# TM1637_Display-Board_simple.net
KiCad netlist of a schematic drawn in EAGLE
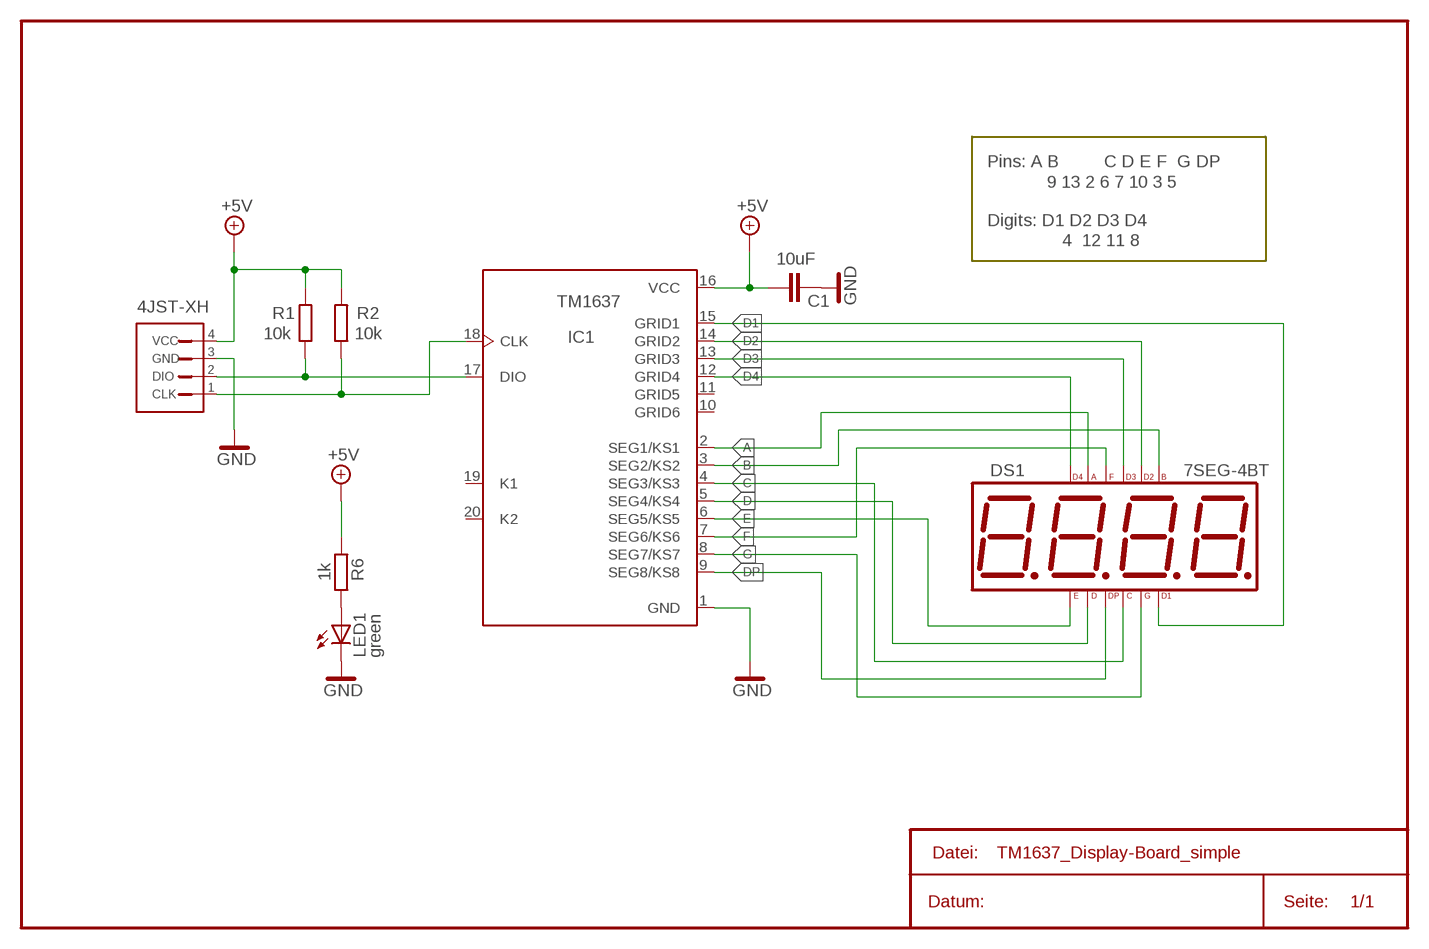
[diagram p0: schematic, sheet 1]

(export (version "E")
  (design (tool "Eeschema 10.0.6"))
  (components
    (comp (ref "1")
      (value "4JST-XH")
      (footprint "eagle-import:4JST-XH")
      (libsource (lib "eagle-import") (part "4JST-XH"))
    )
    (comp (ref "C1")
      (value "10uF")
      (footprint "eagle-import:C0805")
      (libsource (lib "eagle-import") (part "C-EUC0805"))
    )
    (comp (ref "DS1")
      (value "7SEG-4BT")
      (footprint "eagle-import:7SEG-14-4BIT")
      (libsource (lib "eagle-import") (part "7SEG-4BT"))
    )
    (comp (ref "IC1")
      (value "TM1637")
      (footprint "eagle-import:SOP-20")
      (libsource (lib "eagle-import") (part "TM1637"))
    )
    (comp (ref "LED1")
      (value "green")
      (footprint "eagle-import:CHIPLED_0603")
      (libsource (lib "eagle-import") (part "LEDCHIPLED_0603"))
    )
    (comp (ref "R1")
      (value "10k")
      (footprint "eagle-import:R0603")
      (libsource (lib "eagle-import") (part "R-EU_R0603"))
    )
    (comp (ref "R2")
      (value "10k")
      (footprint "eagle-import:R0603")
      (libsource (lib "eagle-import") (part "R-EU_R0603"))
    )
    (comp (ref "R6")
      (value "1k")
      (footprint "eagle-import:R0603")
      (libsource (lib "eagle-import") (part "R-EU_R0603"))
    )
  )
  (nets
    (net (code "1") (name "+5V") (class "Default")
      (node (ref "1") (pin "1") (pinfunction "1_1") (pintype "passive"))
      (node (ref "C1") (pin "1") (pinfunction "1_1") (pintype "passive"))
      (node (ref "IC1") (pin "16") (pinfunction "VCC_16") (pintype "bidirectional"))
      (node (ref "R1") (pin "2") (pinfunction "2_2") (pintype "passive"))
      (node (ref "R2") (pin "2") (pinfunction "2_2") (pintype "passive"))
      (node (ref "R6") (pin "1") (pinfunction "1_1") (pintype "passive"))
    )
    (net (code "2") (name "A") (class "Default")
      (node (ref "DS1") (pin "A") (pinfunction "A_A") (pintype "bidirectional"))
      (node (ref "IC1") (pin "2") (pinfunction "SEG1/KS1_2") (pintype "bidirectional"))
    )
    (net (code "3") (name "B") (class "Default")
      (node (ref "DS1") (pin "B") (pinfunction "B_B") (pintype "bidirectional"))
      (node (ref "IC1") (pin "3") (pinfunction "SEG2/KS2_3") (pintype "bidirectional"))
    )
    (net (code "4") (name "C") (class "Default")
      (node (ref "DS1") (pin "C") (pinfunction "C_C") (pintype "bidirectional"))
      (node (ref "IC1") (pin "4") (pinfunction "SEG3/KS3_4") (pintype "bidirectional"))
    )
    (net (code "5") (name "D") (class "Default")
      (node (ref "DS1") (pin "D") (pinfunction "D_D") (pintype "bidirectional"))
      (node (ref "IC1") (pin "5") (pinfunction "SEG4/KS4_5") (pintype "bidirectional"))
    )
    (net (code "6") (name "D1") (class "Default")
      (node (ref "DS1") (pin "D1") (pinfunction "D1_D1") (pintype "bidirectional"))
      (node (ref "IC1") (pin "15") (pinfunction "GRID1_15") (pintype "bidirectional"))
    )
    (net (code "7") (name "D2") (class "Default")
      (node (ref "DS1") (pin "D2") (pinfunction "D2_D2") (pintype "bidirectional"))
      (node (ref "IC1") (pin "14") (pinfunction "GRID2_14") (pintype "bidirectional"))
    )
    (net (code "8") (name "D3") (class "Default")
      (node (ref "DS1") (pin "D3") (pinfunction "D3_D3") (pintype "bidirectional"))
      (node (ref "IC1") (pin "13") (pinfunction "GRID3_13") (pintype "bidirectional"))
    )
    (net (code "9") (name "D4") (class "Default")
      (node (ref "DS1") (pin "D4") (pinfunction "D4_D4") (pintype "bidirectional"))
      (node (ref "IC1") (pin "12") (pinfunction "GRID4_12") (pintype "bidirectional"))
    )
    (net (code "10") (name "DP") (class "Default")
      (node (ref "DS1") (pin "DP") (pinfunction "DP_DP") (pintype "bidirectional"))
      (node (ref "IC1") (pin "9") (pinfunction "SEG8/KS8_9") (pintype "bidirectional"))
    )
    (net (code "11") (name "E") (class "Default")
      (node (ref "DS1") (pin "E") (pinfunction "E_E") (pintype "bidirectional"))
      (node (ref "IC1") (pin "6") (pinfunction "SEG5/KS5_6") (pintype "bidirectional"))
    )
    (net (code "12") (name "F") (class "Default")
      (node (ref "DS1") (pin "F") (pinfunction "F_F") (pintype "bidirectional"))
      (node (ref "IC1") (pin "7") (pinfunction "SEG6/KS6_7") (pintype "bidirectional"))
    )
    (net (code "13") (name "G") (class "Default")
      (node (ref "DS1") (pin "G") (pinfunction "G_G") (pintype "bidirectional"))
      (node (ref "IC1") (pin "8") (pinfunction "SEG7/KS7_8") (pintype "bidirectional"))
    )
    (net (code "14") (name "GND") (class "Default")
      (node (ref "1") (pin "2") (pinfunction "1_2") (pintype "passive"))
      (node (ref "C1") (pin "2") (pinfunction "2_2") (pintype "passive"))
      (node (ref "IC1") (pin "1") (pinfunction "GND_1") (pintype "bidirectional"))
      (node (ref "LED1") (pin "C") (pinfunction "C_C") (pintype "passive"))
    )
    (net (code "15") (name "Net-(1C-1)") (class "Default")
      (node (ref "1") (pin "3") (pinfunction "1_3") (pintype "passive"))
      (node (ref "IC1") (pin "17") (pinfunction "DIO_17") (pintype "bidirectional"))
      (node (ref "R1") (pin "1") (pinfunction "1_1") (pintype "passive"))
    )
    (net (code "16") (name "Net-(1D-1)") (class "Default")
      (node (ref "1") (pin "4") (pinfunction "1_4") (pintype "passive"))
      (node (ref "IC1") (pin "18") (pinfunction "CLK_18") (pintype "bidirectional"))
      (node (ref "R2") (pin "1") (pinfunction "1_1") (pintype "passive"))
    )
    (net (code "17") (name "Net-(LED1-PadA)") (class "Default")
      (node (ref "LED1") (pin "A") (pinfunction "A_A") (pintype "passive"))
      (node (ref "R6") (pin "2") (pinfunction "2_2") (pintype "passive"))
    )
    (net (code "18") (name "unconnected-(IC1-GRID5-Pad11)") (class "Default")
      (node (ref "IC1") (pin "11") (pinfunction "GRID5_11") (pintype "bidirectional"))
    )
    (net (code "19") (name "unconnected-(IC1-GRID6-Pad10)") (class "Default")
      (node (ref "IC1") (pin "10") (pinfunction "GRID6_10") (pintype "bidirectional"))
    )
    (net (code "20") (name "unconnected-(IC1-K1-Pad19)") (class "Default")
      (node (ref "IC1") (pin "19") (pinfunction "K1_19") (pintype "bidirectional"))
    )
    (net (code "21") (name "unconnected-(IC1-K2-Pad20)") (class "Default")
      (node (ref "IC1") (pin "20") (pinfunction "K2_20") (pintype "bidirectional"))
    )
  )
)
